# Sheet1.net
KiCad netlist of a schematic drawn in Altium Designer
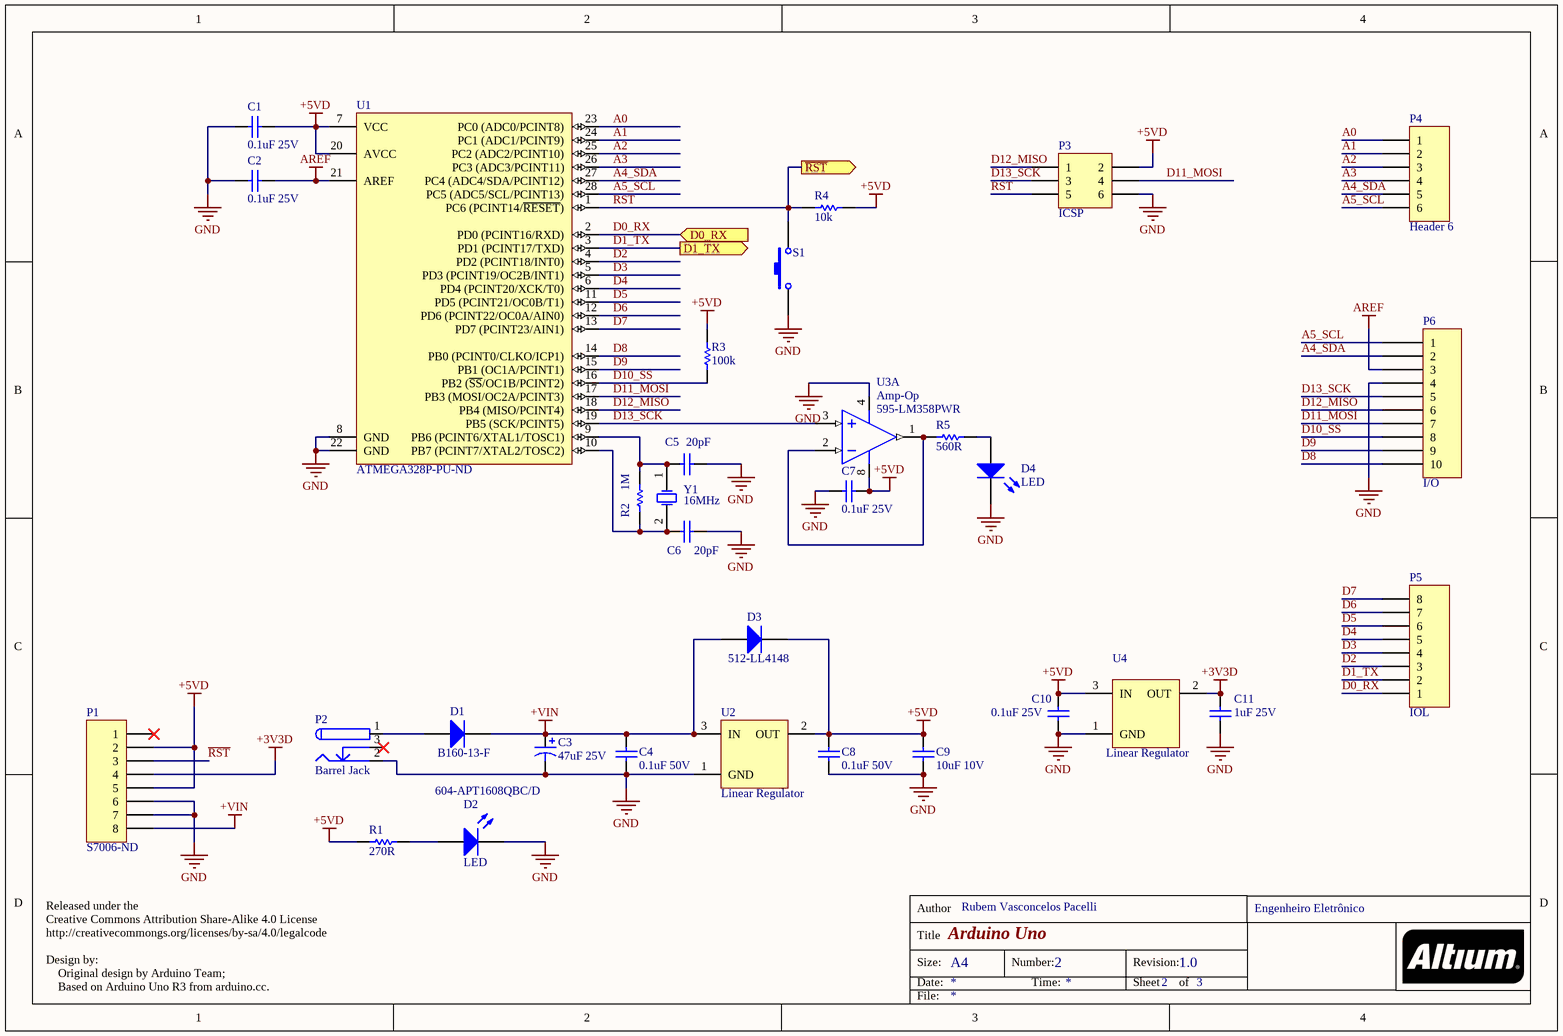
[diagram p0: Sheet1.SchDoc]

(export (version "E")
  (design (tool "Eeschema 10.0.6"))
  (components
    (comp (ref "C1")
      (value "0.1uF 25V")
      (footprint "C1608[0603]")
      (description "Capacitor Decoupling")
      (fields (field (name "MANUFACTURER PART NUMBER") "GCM188R71E104KA57D") (field (name "TOLERANCE") "10%"))
      (libsource (lib "Basic Library") (part "C"))
    )
    (comp (ref "C2")
      (value "0.1uF 25V")
      (footprint "C1608[0603]")
      (description "Capacitor Decoupling")
      (fields (field (name "MANUFACTURER PART NUMBER") "GCM188R71E104KA57D") (field (name "TOLERANCE") "10%"))
      (libsource (lib "Basic Library") (part "C"))
    )
    (comp (ref "C3")
      (value "47uF 25V")
      (footprint "Cap_Al_SMD_C6_6.6x6.6mm")
      (description "Polarized Capacitor - Power Entry")
      (fields (field (name "MANUFACTURER PART NUMBER") "EEE-HA1E470WP") (field (name "TOLERANCE") "20%"))
      (libsource (lib "Basic Library") (part "CP"))
    )
    (comp (ref "C4")
      (value "0.1uF 50V")
      (footprint "C1608[0603]")
      (description "Decoupling Capacitor")
      (fields
        (field (name "MANUFACTURER PART NUMBER") "C1608X7R1H104M080AA")
        (field (name "TOLERANCE") "20%")
      )
      (libsource (lib "Basic Library") (part "C"))
    )
    (comp (ref "C5")
      (value "20pF")
      (footprint "C1608[0603]")
      (description "Capacitor Crystal")
      (fields (field (name "MANUFACTURER PART NUMBER") "CL10C200JB8NNNC") (field (name "TOLERANCE") "5%"))
      (libsource (lib "Basic Library") (part "C"))
    )
    (comp (ref "C6")
      (value "20pF")
      (footprint "C1608[0603]")
      (description "Capacitor Crystal")
      (fields (field (name "MANUFACTURER PART NUMBER") "CL10C200JB8NNNC") (field (name "TOLERANCE") "5%"))
      (libsource (lib "Basic Library") (part "C"))
    )
    (comp (ref "C7")
      (value "0.1uF 25V")
      (footprint "C1608[0603]")
      (description "Capacitor Decoupling")
      (fields (field (name "MANUFACTURER PART NUMBER") "GCM188R71E104KA57D") (field (name "TOLERANCE") "10%"))
      (libsource (lib "Basic Library") (part "C"))
    )
    (comp (ref "C8")
      (value "0.1uF 50V")
      (footprint "C1608[0603]")
      (description "Capacitor Decoupling")
      (fields
        (field (name "MANUFACTURER PART NUMBER") "C1608X7R1H104M080AA")
        (field (name "TOLERANCE") "20%")
      )
      (libsource (lib "Basic Library") (part "C"))
    )
    (comp (ref "C9")
      (value "10uF 10V")
      (footprint "C2012[0805]")
      (description "Capacitor Decoupling")
      (fields (field (name "MANUFACTURER PART NUMBER") "C1608JB1A106K080AC") (field (name "TOLERANCE") "10%"))
      (libsource (lib "Basic Library") (part "C"))
    )
    (comp (ref "C10")
      (value "0.1uF 25V")
      (footprint "C1608[0603]")
      (description "Capacitor Decoupling")
      (fields (field (name "MANUFACTURER PART NUMBER") "GCM188R71E104KA57D") (field (name "TOLERANCE") "10%"))
      (libsource (lib "Basic Library") (part "C"))
    )
    (comp (ref "C11")
      (value "1uF 25V")
      (footprint "C2012[0805]")
      (description "Capacitor Decoupling")
      (fields
        (field (name "MANUFACTURER") "TDK")
        (field (name "MANUFACTURER PART NUMBER") "C2012X7R1E105K125AB")
      )
      (libsource (lib "Basic Library") (part "C"))
    )
    (comp (ref "D1")
      (value "B160-13-F")
      (footprint "DO214AC")
      (description "Diode")
      (fields (field (name "MANUFACTURER PART NUMBER") "B160-13-F"))
      (libsource (lib "Basic Library") (part "D"))
    )
    (comp (ref "D2")
      (value "LED")
      (footprint "LED-0603-G")
      (description "LED indicador visual")
      (fields
        (field (name "MANUFACTURER") "Kingbright")
        (field (name "SUPPLIER PART NUMBER 1") "604-APT1608QBC/D")
        (field (name "MANUFACTURER PART NUMBER") "APT1608QBC/D")
      )
      (libsource (lib "Basic Library") (part "LED"))
    )
    (comp (ref "D3")
      (value "~")
      (footprint "SOD-80/MLL34")
      (description "Diode Protection")
      (fields
        (field (name "SUPPLIER PART NUMBER 1") "512-LL4148")
        (field (name "MANUFACTURER PART NUMBER") "LL4148")
        (field (name "VOLTAGE") "100V")
      )
      (libsource (lib "Basic Library") (part "D"))
    )
    (comp (ref "D4")
      (value "LED")
      (footprint "LED-0603-R")
      (fields (field (name "MANUFACTURER PART NUMBER") "LTST-C191KRKT") (field (name "VOLTAGE") "2V"))
      (libsource (lib "Basic Library") (part "LED"))
    )
    (comp (ref "P1")
      (value "Header 8")
      (footprint "HDR1X8F")
      (description "Header, 8-Pin")
      (fields
        (field (name "SUPPLIER PART NUMBER 1") "S7006-ND")
        (field (name "MANUFACTURER") "Sullins")
        (field (name "MANUFACTURER PART NUMBER") "PPTC081LFBN-RC")
        (field (name "PUBLISHER") "Altium Limited")
      )
      (libsource (lib "") (part "Header 8_1"))
    )
    (comp (ref "P2")
      (value "Barrel Jack")
      (footprint "BARREL2.5")
      (description "Low Voltage Power Supply Connector")
      (fields
        (field (name "MANUFACTURER") "Memory Protection Devices")
        (field (name "MANUFACTURER PART NUMBER") "EJ503A")
      )
      (libsource (lib "Connectors Library") (part "PWR2.5"))
    )
    (comp (ref "P3")
      (value "ICSP")
      (footprint "HDR2X3M")
      (description "Header, 3-Pin, Dual row")
      (fields
        (field (name "MANUFACTURER") "Harwin")
        (field (name "MANUFACTURER PART NUMBER") "M20-9720345")
        (field (name "PUBLISHER") "Altium Limited")
      )
      (libsource (lib "Connectors Library") (part "Header 3X2"))
    )
    (comp (ref "P4")
      (value "Header 6")
      (footprint "HDR1X6F")
      (description "Header, 6-Pin")
      (fields (field (name "PUBLISHER") "Altium Limited"))
      (libsource (lib "Connectors Library") (part "Header 6"))
    )
    (comp (ref "P5")
      (value "IOL")
      (footprint "HDR1X8F")
      (description "Header, 8-Pin")
      (fields
        (field (name "MANUFACTURER") "Sullins")
        (field (name "MANUFACTURER PART NUMBER") "PPTC081LFBN-RC")
        (field (name "PUBLISHER") "Altium Limited")
      )
      (libsource (lib "Connectors Library") (part "Header 8"))
    )
    (comp (ref "P6")
      (value "I/O")
      (footprint "HDR1X10")
      (description "Header, 10-Pin")
      (fields
        (field (name "MANUFACTURER") "Sullins")
        (field (name "MANUFACTURER PART NUMBER") "PPTC101LFBN-RC")
      )
      (libsource (lib "Connectors Library") (part "Header 10"))
    )
    (comp (ref "R1")
      (value "270R")
      (footprint "R1608[0603]")
      (description "Resistor")
      (fields
        (field (name "MANUFACTURER") "Rohm Semiconductor")
        (field (name "MANUFACTURER PART NUMBER") "ESR03EZPJ271")
      )
      (libsource (lib "Basic Library") (part "R"))
    )
    (comp (ref "R2")
      (value "1M")
      (footprint "R2012[0805]")
      (description "Resistor")
      (fields (field (name "MANUFACTURER PART NUMBER") "ERA-6AEB105V") (field (name "TOLERANCE") "1%"))
      (libsource (lib "Basic Library") (part "R"))
    )
    (comp (ref "R3")
      (value "100k")
      (footprint "R1608[0603]")
      (description "Resistor pull-up")
      (fields (field (name "MANUFACTURER PART NUMBER") "MCT06030C1003FP500") (field (name "TOLERANCE") "1%"))
      (libsource (lib "Basic Library") (part "R"))
    )
    (comp (ref "R4")
      (value "10k")
      (footprint "R1608[0603]")
      (description "Resistor pull-up")
      (fields (field (name "MANUFACTURER PART NUMBER") "MCT06030C1002FP500") (field (name "TOLERANCE") "1%"))
      (libsource (lib "Basic Library") (part "R"))
    )
    (comp (ref "R5")
      (value "560R")
      (footprint "R1608[0603]")
      (description "Resistor")
      (fields (field (name "MANUFACTURER PART NUMBER") "AC0603FR-07560RL") (field (name "TOLERANCE") "1%"))
      (libsource (lib "Basic Library") (part "R"))
    )
    (comp (ref "S1")
      (value "~")
      (footprint "PB-SW-SMT")
      (description "Tactile Switch")
      (fields (field (name "MANUFACTURER PART NUMBER") "PTS645SM43SMTR92LFS"))
      (libsource (lib "Basic Library") (part "SW Tact"))
    )
    (comp (ref "U1")
      (value "ATmega328P-PU")
      (footprint "DIP28")
      (fields
        (field (name "SUPPLIER PART NUMBER 1") "ATMEGA328P-PU-ND")
        (field (name "MANUFACTURER") "Microchip / Atmel")
        (field (name "MANUFACTURER PART NUMBER") "ATMEGA328P-PU")
      )
      (libsource (lib "Components Library") (part "ATmega328P-PU"))
    )
    (comp (ref "U2")
      (value "Linear Regulator")
      (footprint "SOT223_N")
      (description "5V supplier")
      (fields (field (name "MANUFACTURER PART NUMBER") "NCP1117ST50T3G") (field (name "TOLERANCE") "1%"))
      (libsource (lib "Basic Library") (part "Regulator"))
    )
    (comp (ref "U3")
      (value "Amp-Op")
      (footprint "TSSOP8")
      (fields
        (field (name "MANUFACTURER") "Texas Instruments")
        (field (name "MANUFACTURER PART NUMBER") "LM358PWR")
        (field (name "SUPPLIER PART NUMBER 1") "595-LM358PWR")
      )
      (libsource (lib "Components Library") (part "LM358PWR"))
    )
    (comp (ref "U4")
      (value "Linear Regulator")
      (footprint "SOT223_N")
      (description "3V3 supplier")
      (fields
        (field (name "MANUFACTURER") "ON Semiconductor")
        (field (name "MANUFACTURER PART NUMBER") "NCP1117ST33T3G")
      )
      (libsource (lib "Symbols") (part "Regulator"))
    )
    (comp (ref "Y1")
      (value "16MHz")
      (footprint "CRYSTAL-HC49/4H_SMX")
      (description "Crystal Oscillator")
      (fields (field (name "MANUFACTURER PART NUMBER") "ECS-160-20-3X-TR") (field (name "TOLERANCE") "30ppm"))
      (libsource (lib "Basic Library") (part "XTAL"))
    )
  )
  (nets
    (net (code "1") (name "+3V3D") (class "Default")
      (node (ref "C11") (pin "2") (pinfunction "2_2") (pintype "passive"))
      (node (ref "P1") (pin "4") (pinfunction "4_4") (pintype "passive"))
      (node (ref "U4") (pin "2") (pinfunction "OUT_2") (pintype "passive"))
    )
    (net (code "2") (name "+5VD") (class "Default")
      (node (ref "C1") (pin "1") (pinfunction "1_1") (pintype "passive"))
      (node (ref "C10") (pin "2") (pinfunction "2_2") (pintype "passive"))
      (node (ref "C7") (pin "1") (pinfunction "1_1") (pintype "passive"))
      (node (ref "C8") (pin "2") (pinfunction "2_2") (pintype "passive"))
      (node (ref "C9") (pin "2") (pinfunction "2_2") (pintype "passive"))
      (node (ref "D3") (pin "2") (pinfunction "K_2") (pintype "passive"))
      (node (ref "P1") (pin "2") (pinfunction "2_2") (pintype "passive"))
      (node (ref "P1") (pin "5") (pinfunction "5_5") (pintype "passive"))
      (node (ref "P3") (pin "2") (pinfunction "2_2") (pintype "passive"))
      (node (ref "R1") (pin "1") (pinfunction "1_1") (pintype "passive"))
      (node (ref "R3") (pin "1") (pinfunction "1_1") (pintype "passive"))
      (node (ref "R4") (pin "1") (pinfunction "1_1") (pintype "passive"))
      (node (ref "U1") (pin "20") (pinfunction "AVCC_20") (pintype "power_in"))
      (node (ref "U1") (pin "7") (pinfunction "VCC_7") (pintype "power_in"))
      (node (ref "U2") (pin "2") (pinfunction "OUT_2") (pintype "passive"))
      (node (ref "U3") (pin "8") (pinfunction "V+_8") (pintype "power_in"))
      (node (ref "U4") (pin "3") (pinfunction "IN_3") (pintype "passive"))
    )
    (net (code "3") (name "+VIN") (class "Default")
      (node (ref "C3") (pin "1") (pinfunction "1_1") (pintype "passive"))
      (node (ref "C4") (pin "2") (pinfunction "2_2") (pintype "passive"))
      (node (ref "D1") (pin "2") (pinfunction "K_2") (pintype "passive"))
      (node (ref "D3") (pin "1") (pinfunction "A_1") (pintype "passive"))
      (node (ref "P1") (pin "8") (pinfunction "8_8") (pintype "passive"))
      (node (ref "U2") (pin "3") (pinfunction "IN_3") (pintype "passive"))
    )
    (net (code "4") (name "/A0") (class "Default")
      (node (ref "P4") (pin "1") (pinfunction "1_1") (pintype "passive"))
      (node (ref "U1") (pin "23") (pinfunction "PC0_(ADC0/PCINT8)_23") (pintype "bidirectional"))
    )
    (net (code "5") (name "/A1") (class "Default")
      (node (ref "P4") (pin "2") (pinfunction "2_2") (pintype "passive"))
      (node (ref "U1") (pin "24") (pinfunction "PC1_(ADC1/PCINT9)_24") (pintype "bidirectional"))
    )
    (net (code "6") (name "/A2") (class "Default")
      (node (ref "P4") (pin "3") (pinfunction "3_3") (pintype "passive"))
      (node (ref "U1") (pin "25") (pinfunction "PC2_(ADC2/PCINT10)_25") (pintype "bidirectional"))
    )
    (net (code "7") (name "/A3") (class "Default")
      (node (ref "P4") (pin "4") (pinfunction "4_4") (pintype "passive"))
      (node (ref "U1") (pin "26") (pinfunction "PC3_(ADC3/PCINT11)_26") (pintype "bidirectional"))
    )
    (net (code "8") (name "/A4_SDA") (class "Default")
      (node (ref "P4") (pin "5") (pinfunction "5_5") (pintype "passive"))
      (node (ref "P6") (pin "2") (pinfunction "2_2") (pintype "passive"))
      (node (ref "U1") (pin "27") (pinfunction "PC4_(ADC4/SDA/PCINT12)_27") (pintype "bidirectional"))
    )
    (net (code "9") (name "/A5_SCL") (class "Default")
      (node (ref "P4") (pin "6") (pinfunction "6_6") (pintype "passive"))
      (node (ref "P6") (pin "1") (pinfunction "1_1") (pintype "passive"))
      (node (ref "U1") (pin "28") (pinfunction "PC5_(ADC5/SCL/PCINT13)_28") (pintype "bidirectional"))
    )
    (net (code "10") (name "/D0_RX") (class "Default")
      (node (ref "P5") (pin "1") (pinfunction "1_1") (pintype "passive"))
      (node (ref "U1") (pin "2") (pinfunction "PD0_(PCINT16/RXD)_2") (pintype "bidirectional"))
    )
    (net (code "11") (name "/D1_TX") (class "Default")
      (node (ref "P5") (pin "2") (pinfunction "2_2") (pintype "passive"))
      (node (ref "U1") (pin "3") (pinfunction "PD1_(PCINT17/TXD)_3") (pintype "bidirectional"))
    )
    (net (code "12") (name "/D2") (class "Default")
      (node (ref "P5") (pin "3") (pinfunction "3_3") (pintype "passive"))
      (node (ref "U1") (pin "4") (pinfunction "PD2_(PCINT18/INT0)_4") (pintype "bidirectional"))
    )
    (net (code "13") (name "/D3") (class "Default")
      (node (ref "P5") (pin "4") (pinfunction "4_4") (pintype "passive"))
      (node (ref "U1") (pin "5") (pinfunction "PD3_(PCINT19/OC2B/INT1)_5") (pintype "bidirectional"))
    )
    (net (code "14") (name "/D4") (class "Default")
      (node (ref "P5") (pin "5") (pinfunction "5_5") (pintype "passive"))
      (node (ref "U1") (pin "6") (pinfunction "PD4_(PCINT20/XCK/T0)_6") (pintype "bidirectional"))
    )
    (net (code "15") (name "/D5") (class "Default")
      (node (ref "P5") (pin "6") (pinfunction "6_6") (pintype "passive"))
      (node (ref "U1") (pin "11") (pinfunction "PD5_(PCINT21/OC0B/T1)_11") (pintype "bidirectional"))
    )
    (net (code "16") (name "/D6") (class "Default")
      (node (ref "P5") (pin "7") (pinfunction "7_7") (pintype "passive"))
      (node (ref "U1") (pin "12") (pinfunction "PD6_(PCINT22/OC0A/AIN0)_12") (pintype "bidirectional"))
    )
    (net (code "17") (name "/D7") (class "Default")
      (node (ref "P5") (pin "8") (pinfunction "8_8") (pintype "passive"))
      (node (ref "U1") (pin "13") (pinfunction "PD7_(PCINT23/AIN1)_13") (pintype "bidirectional"))
    )
    (net (code "18") (name "/D8") (class "Default")
      (node (ref "P6") (pin "10") (pinfunction "10_10") (pintype "passive"))
      (node (ref "U1") (pin "14") (pinfunction "PB0_(PCINT0/CLKO/ICP1)_14") (pintype "bidirectional"))
    )
    (net (code "19") (name "/D9") (class "Default")
      (node (ref "P6") (pin "9") (pinfunction "9_9") (pintype "passive"))
      (node (ref "U1") (pin "15") (pinfunction "PB1_(OC1A/PCINT1)_15") (pintype "bidirectional"))
    )
    (net (code "20") (name "/D10_SS") (class "Default")
      (node (ref "P6") (pin "8") (pinfunction "8_8") (pintype "passive"))
      (node (ref "R3") (pin "2") (pinfunction "2_2") (pintype "passive"))
      (node (ref "U1") (pin "16") (pinfunction "PB2_(~{SS}/OC1B/PCINT2)_16") (pintype "bidirectional"))
    )
    (net (code "21") (name "/D11_MOSI") (class "Default")
      (node (ref "P3") (pin "4") (pinfunction "4_4") (pintype "passive"))
      (node (ref "P6") (pin "7") (pinfunction "7_7") (pintype "passive"))
      (node (ref "U1") (pin "17") (pinfunction "PB3_(MOSI/OC2A/PCINT3)_17") (pintype "bidirectional"))
    )
    (net (code "22") (name "/D12_MISO") (class "Default")
      (node (ref "P3") (pin "1") (pinfunction "1_1") (pintype "passive"))
      (node (ref "P6") (pin "6") (pinfunction "6_6") (pintype "passive"))
      (node (ref "U1") (pin "18") (pinfunction "PB4_(MISO/PCINT4)_18") (pintype "bidirectional"))
    )
    (net (code "23") (name "/D13_SCK") (class "Default")
      (node (ref "P3") (pin "3") (pinfunction "3_3") (pintype "passive"))
      (node (ref "P6") (pin "5") (pinfunction "5_5") (pintype "passive"))
      (node (ref "U1") (pin "19") (pinfunction "PB5_(SCK/PCINT5)_19") (pintype "bidirectional"))
      (node (ref "U3") (pin "3") (pinfunction "IN1+_3") (pintype "input"))
    )
    (net (code "24") (name "/~{RST}") (class "Default")
      (node (ref "P1") (pin "3") (pinfunction "3_3") (pintype "passive"))
      (node (ref "P3") (pin "5") (pinfunction "5_5") (pintype "passive"))
      (node (ref "R4") (pin "2") (pinfunction "2_2") (pintype "passive"))
      (node (ref "S1") (pin "2") (pinfunction "2_2") (pintype "passive"))
      (node (ref "U1") (pin "1") (pinfunction "PC6_(PCINT14/~{RESET})_1") (pintype "bidirectional"))
    )
    (net (code "25") (name "AREF") (class "Default")
      (node (ref "C2") (pin "1") (pinfunction "1_1") (pintype "passive"))
      (node (ref "P6") (pin "3") (pinfunction "3_3") (pintype "passive"))
      (node (ref "U1") (pin "21") (pinfunction "AREF_21") (pintype "power_in"))
    )
    (net (code "26") (name "GND") (class "Default")
      (node (ref "C1") (pin "2") (pinfunction "2_2") (pintype "passive"))
      (node (ref "C10") (pin "1") (pinfunction "1_1") (pintype "passive"))
      (node (ref "C11") (pin "1") (pinfunction "1_1") (pintype "passive"))
      (node (ref "C2") (pin "2") (pinfunction "2_2") (pintype "passive"))
      (node (ref "C3") (pin "2") (pinfunction "2_2") (pintype "passive"))
      (node (ref "C4") (pin "1") (pinfunction "1_1") (pintype "passive"))
      (node (ref "C5") (pin "2") (pinfunction "2_2") (pintype "passive"))
      (node (ref "C6") (pin "2") (pinfunction "2_2") (pintype "passive"))
      (node (ref "C7") (pin "2") (pinfunction "2_2") (pintype "passive"))
      (node (ref "C8") (pin "1") (pinfunction "1_1") (pintype "passive"))
      (node (ref "C9") (pin "1") (pinfunction "1_1") (pintype "passive"))
      (node (ref "D2") (pin "2") (pinfunction "K_2") (pintype "passive"))
      (node (ref "D4") (pin "2") (pinfunction "K_2") (pintype "passive"))
      (node (ref "P1") (pin "6") (pinfunction "6_6") (pintype "passive"))
      (node (ref "P1") (pin "7") (pinfunction "7_7") (pintype "passive"))
      (node (ref "P2") (pin "2") (pinfunction "2_2") (pintype "passive"))
      (node (ref "P3") (pin "6") (pinfunction "6_6") (pintype "passive"))
      (node (ref "P6") (pin "4") (pinfunction "4_4") (pintype "passive"))
      (node (ref "S1") (pin "1") (pinfunction "1_1") (pintype "passive"))
      (node (ref "U1") (pin "22") (pinfunction "GND_22") (pintype "power_in"))
      (node (ref "U1") (pin "8") (pinfunction "GND_8") (pintype "power_in"))
      (node (ref "U2") (pin "1") (pinfunction "GND_1") (pintype "passive"))
      (node (ref "U3") (pin "4") (pinfunction "GND_4") (pintype "power_in"))
      (node (ref "U4") (pin "1") (pinfunction "GND_1") (pintype "passive"))
    )
    (net (code "27") (name "Net-(D1-A)") (class "Default")
      (node (ref "D1") (pin "1") (pinfunction "A_1") (pintype "passive"))
      (node (ref "P2") (pin "1") (pinfunction "1_1") (pintype "passive"))
    )
    (net (code "28") (name "Net-(D2-A)") (class "Default")
      (node (ref "D2") (pin "1") (pinfunction "A_1") (pintype "passive"))
      (node (ref "R1") (pin "2") (pinfunction "2_2") (pintype "passive"))
    )
    (net (code "29") (name "Net-(D4-A)") (class "Default")
      (node (ref "D4") (pin "1") (pinfunction "A_1") (pintype "passive"))
      (node (ref "R5") (pin "2") (pinfunction "2_2") (pintype "passive"))
    )
    (net (code "30") (name "Net-(U1-PB6_(PCINT6{slash}XTAL1{slash}TOSC1))") (class "Default")
      (node (ref "C5") (pin "1") (pinfunction "1_1") (pintype "passive"))
      (node (ref "R2") (pin "2") (pinfunction "2_2") (pintype "passive"))
      (node (ref "U1") (pin "9") (pinfunction "PB6_(PCINT6/XTAL1/TOSC1)_9") (pintype "bidirectional"))
      (node (ref "Y1") (pin "1") (pinfunction "OSC1_1") (pintype "passive"))
    )
    (net (code "31") (name "Net-(U1-PB7_(PCINT7{slash}XTAL2{slash}TOSC2))") (class "Default")
      (node (ref "C6") (pin "1") (pinfunction "1_1") (pintype "passive"))
      (node (ref "R2") (pin "1") (pinfunction "1_1") (pintype "passive"))
      (node (ref "U1") (pin "10") (pinfunction "PB7_(PCINT7/XTAL2/TOSC2)_10") (pintype "bidirectional"))
      (node (ref "Y1") (pin "2") (pinfunction "OSC2_2") (pintype "passive"))
    )
    (net (code "32") (name "Net-(U3A-IN1-)") (class "Default")
      (node (ref "R5") (pin "1") (pinfunction "1_1") (pintype "passive"))
      (node (ref "U3") (pin "1") (pinfunction "OUT1_1") (pintype "output"))
      (node (ref "U3") (pin "2") (pinfunction "IN1-_2") (pintype "input"))
    )
    (net (code "33") (name "unconnected-(P1-Pad1)") (class "Default")
      (node (ref "P1") (pin "1") (pinfunction "1_1") (pintype "passive+no_connect"))
    )
    (net (code "34") (name "unconnected-(P2-Pad3)") (class "Default")
      (node (ref "P2") (pin "3") (pinfunction "3_3") (pintype "passive+no_connect"))
    )
  )
)
